# 03_-_MPU6050_Schematic.net
KiCad netlist of a schematic drawn in Altium Designer
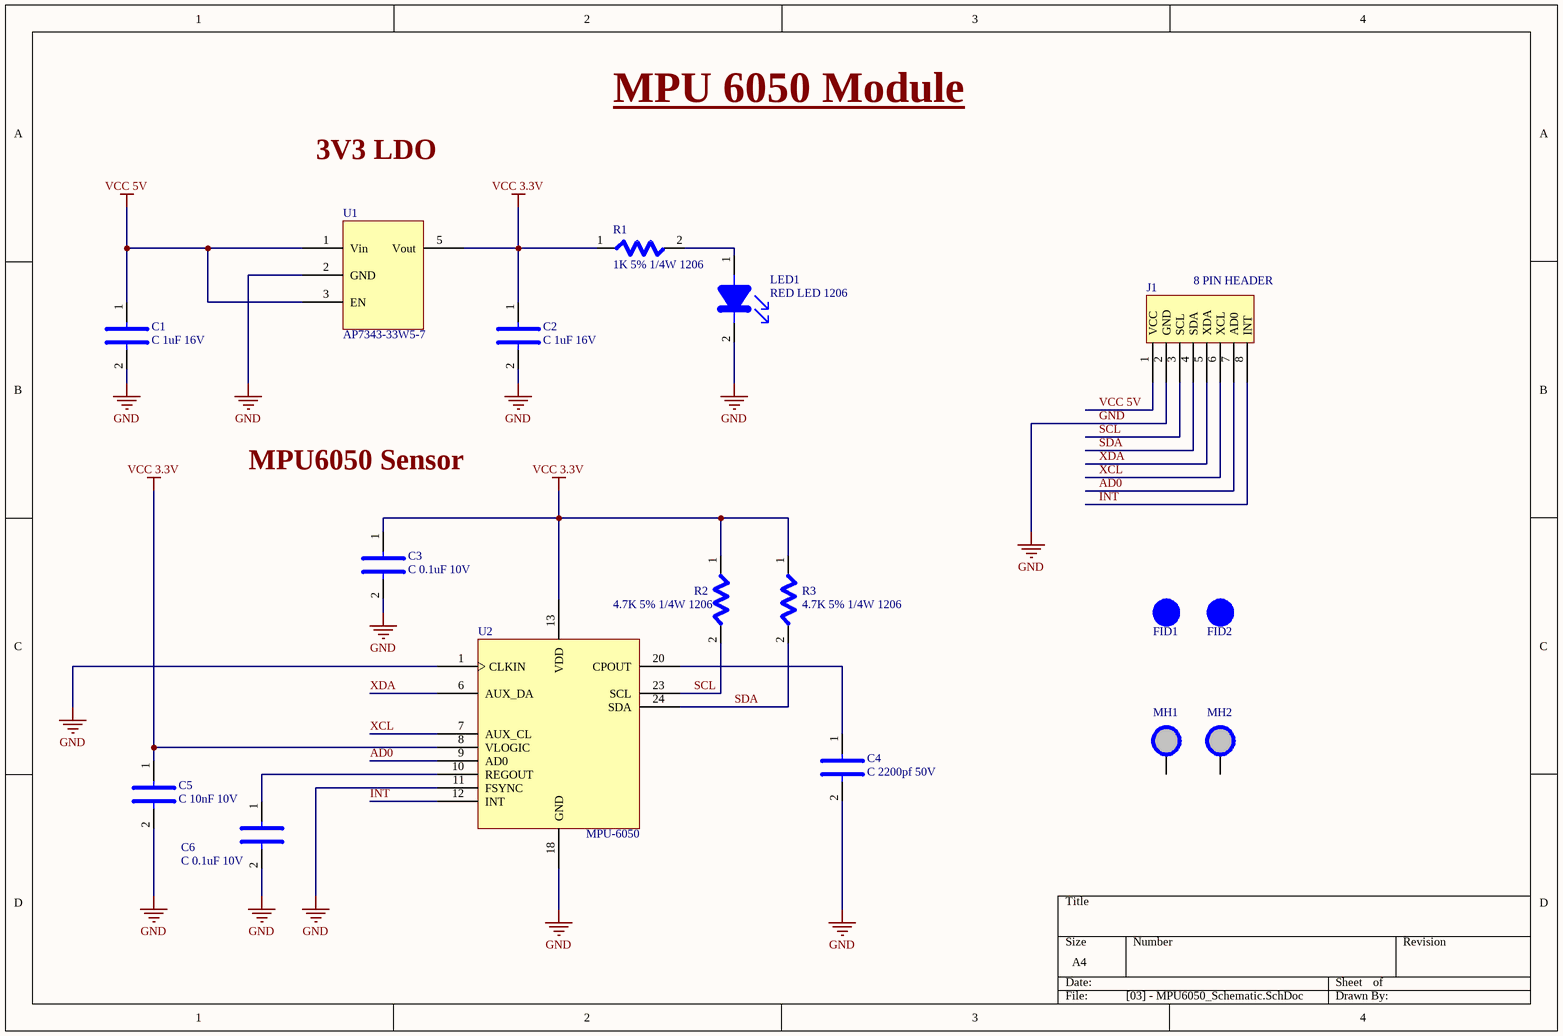
[diagram p0: [03] - MPU6050_Schematic.SchDoc]

(export (version "E")
  (design (tool "Eeschema 10.0.6"))
  (components
    (comp (ref "C1")
      (value "C 1uF 16V")
      (footprint "CAP CER 1UF 10V X7R 1206")
      (description "1 µF ±10% 10V Capacitores cerámicos X7R 1206 (3216 métrico)")
      (fields (field (name "MANUFACTURER") "KEMET"))
      (libsource (lib "MPU6050_SCHLIB") (part "CAP CER 1UF 10V X7R 1206"))
    )
    (comp (ref "C2")
      (value "C 1uF 16V")
      (footprint "CAP CER 1UF 10V X7R 1206")
      (description "1 µF ±10% 10V Capacitores cerámicos X7R 1206 (3216 métrico)")
      (fields (field (name "MANUFACTURER") "KEMET"))
      (libsource (lib "MPU6050_SCHLIB") (part "CAP CER 1UF 10V X7R 1206"))
    )
    (comp (ref "C3")
      (value "C 0.1uF 10V")
      (footprint "CAP CER 0.1UF 10V X7R 1206")
      (description "0.1 µF ±10% 10V Capacitores cerámicos X7R 1206 (3216 métrico)")
      (fields (field (name "MANUFACTURER") "KEMET"))
      (libsource (lib "MPU6050_SCHLIB") (part "CAP CER 0.1UF 10V X7R 1206"))
    )
    (comp (ref "C4")
      (value "C 2200pf 50V")
      (footprint "CAP CER 2200PF 50V NP0 1206")
      (description "CAP CER 2200PF 50V NP0 1206")
      (fields (field (name "MANUFACTURER") "KEMET"))
      (libsource (lib "MPU6050_SCHLIB") (part "CAP CER 2200PF 50V NP0 1206"))
    )
    (comp (ref "C5")
      (value "C 10nF 10V")
      (footprint "CAP CER 1206 10NF 10V ULTRA STAB")
      (description "10000 pF ±1% 10V Capacitores cerámicos X8R 1206 (3216 métrico)")
      (fields (field (name "MANUFACTURER") "KEMET"))
      (libsource (lib "MPU6050_SCHLIB") (part "CAP CER 1206 10NF 10V ULTRA STAB"))
    )
    (comp (ref "C6")
      (value "C 0.1uF 10V")
      (footprint "CAP CER 0.1UF 10V X7R 1206")
      (description "0.1 µF ±10% 10V Capacitores cerámicos X7R 1206 (3216 métrico)")
      (fields (field (name "MANUFACTURER") "KEMET"))
      (libsource (lib "MPU6050_SCHLIB") (part "CAP CER 0.1UF 10V X7R 1206"))
    )
    (comp (ref "FID1")
      (value "FID_1mm")
      (footprint "FID_40_120")
      (description "Fiducial 40mil Diameter, 120mil Mask")
      (libsource (lib "MPU6050_SCHLIB") (part "FID_1mm"))
    )
    (comp (ref "FID2")
      (value "FID_1mm")
      (footprint "FID_40_120")
      (description "Fiducial 40mil Diameter, 120mil Mask")
      (libsource (lib "MPU6050_SCHLIB") (part "FID_1mm"))
    )
    (comp (ref "J1")
      (value "8 PIN HEADER")
      (footprint "CONN HEADER VERT 8POS 3.96MM")
      (description "Cabezal de conector Orificio pasante 8 posiciones 0.156\" (3.96mm)")
      (fields (field (name "MANUFACTURER") "TE Connectivity AMP Connectors"))
      (libsource (lib "MPU6050_SCHLIB") (part "CONN HEADER VERT 8POS 3.96MM"))
    )
    (comp (ref "LED1")
      (value "RED LED 1206")
      (footprint "RES SMD 1K OHM 5% 1/4W 1206")
      (description "Rojo 630nm Indicación led: discreta 1.5V 1206 (3216 métrico)")
      (fields (field (name "MANUFACTURER") "Venkel"))
      (libsource (lib "MPU6050_SCHLIB") (part "LED 1206 FLAT LENS RED"))
    )
    (comp (ref "MH1")
      (value "MH_3.2mmD")
      (footprint "MH 7.4mmD 3.2mmDirll No plated")
      (description "MH 7..4mmD 3.2mmDrill Non plated")
      (libsource (lib "MPU6050_SCHLIB") (part "MH_3.2mmD"))
    )
    (comp (ref "MH2")
      (value "MH_3.2mmD")
      (footprint "MH 7.4mmD 3.2mmDirll No plated")
      (description "MH 7..4mmD 3.2mmDrill Non plated")
      (libsource (lib "MPU6050_SCHLIB") (part "MH_3.2mmD"))
    )
    (comp (ref "R1")
      (value "1K 5% 1/4W 1206")
      (footprint "RES SMD 1K OHM 5% 1/4W 1206")
      (description "1 kOhms ±5% 0.25W, 1/4W Resistencia en microprocesador 1206 (3216 métrico) - Película gruesa")
      (fields (field (name "MANUFACTURER") "Yageo"))
      (libsource (lib "MPU6050_SCHLIB") (part "RES SMD 1K OHM 5% 1/4W 1206"))
    )
    (comp (ref "R2")
      (value "4.7K 5% 1/4W 1206")
      (footprint "RES SMD 4.7K OHM 5% 1/4W 1206")
      (fields (field (name "MANUFACTURER") "Yageo"))
      (libsource (lib "MPU6050_SCHLIB") (part "RES 4.7K OHM 5% 1/4W 1206"))
    )
    (comp (ref "R3")
      (value "4.7K 5% 1/4W 1206")
      (footprint "RES SMD 4.7K OHM 5% 1/4W 1206")
      (fields (field (name "MANUFACTURER") "Yageo"))
      (libsource (lib "MPU6050_SCHLIB") (part "RES 4.7K OHM 5% 1/4W 1206"))
    )
    (comp (ref "U1")
      (value "AP7343-33W5-7")
      (footprint "AP7343-33W5-7")
      (description "Low dropout regulator with high output voltage. 3.3V 300mA")
      (fields (field (name "MANUFACTURER") "DIODES Incorporated"))
      (libsource (lib "MPU6050_SCHLIB") (part "AP7343-33W5-7"))
    )
    (comp (ref "U2")
      (value "MPU-6050")
      (footprint "MPU6050")
      (description "Acelerometer, gyro, 6 axis")
      (fields (field (name "MANUFACTURER") "TDK InvenSense"))
      (libsource (lib "MPU6050_SCHLIB") (part "MPU-6050"))
    )
  )
  (nets
    (net (code "1") (name "/AD0") (class "Default")
      (node (ref "J1") (pin "7") (pinfunction "AD0_7") (pintype "passive"))
      (node (ref "U2") (pin "9") (pinfunction "AD0_9") (pintype "passive"))
    )
    (net (code "2") (name "/INT") (class "Default")
      (node (ref "J1") (pin "8") (pinfunction "INT_8") (pintype "passive"))
      (node (ref "U2") (pin "12") (pinfunction "INT_12") (pintype "passive"))
    )
    (net (code "3") (name "/SCL") (class "Default")
      (node (ref "J1") (pin "3") (pinfunction "SCL_3") (pintype "passive"))
      (node (ref "R2") (pin "2") (pinfunction "2_2") (pintype "passive"))
      (node (ref "U2") (pin "23") (pinfunction "SCL_23") (pintype "passive"))
    )
    (net (code "4") (name "/SDA") (class "Default")
      (node (ref "J1") (pin "4") (pinfunction "SDA_4") (pintype "passive"))
      (node (ref "R3") (pin "2") (pinfunction "2_2") (pintype "passive"))
      (node (ref "U2") (pin "24") (pinfunction "SDA_24") (pintype "passive"))
    )
    (net (code "5") (name "/XCL") (class "Default")
      (node (ref "J1") (pin "6") (pinfunction "XCL_6") (pintype "passive"))
      (node (ref "U2") (pin "7") (pinfunction "AUX_CL_7") (pintype "passive"))
    )
    (net (code "6") (name "/XDA") (class "Default")
      (node (ref "J1") (pin "5") (pinfunction "XDA_5") (pintype "passive"))
      (node (ref "U2") (pin "6") (pinfunction "AUX_DA_6") (pintype "passive"))
    )
    (net (code "7") (name "GND") (class "Default")
      (node (ref "C1") (pin "2") (pinfunction "2_2") (pintype "passive"))
      (node (ref "C2") (pin "2") (pinfunction "2_2") (pintype "passive"))
      (node (ref "C3") (pin "2") (pinfunction "2_2") (pintype "passive"))
      (node (ref "C4") (pin "2") (pinfunction "2_2") (pintype "passive"))
      (node (ref "C5") (pin "2") (pinfunction "2_2") (pintype "passive"))
      (node (ref "C6") (pin "2") (pinfunction "2_2") (pintype "passive"))
      (node (ref "J1") (pin "2") (pinfunction "GND_2") (pintype "passive"))
      (node (ref "LED1") (pin "2") (pinfunction "2_2") (pintype "passive"))
      (node (ref "U1") (pin "2") (pinfunction "GND_2") (pintype "passive"))
      (node (ref "U2") (pin "1") (pinfunction "CLKIN_1") (pintype "passive"))
      (node (ref "U2") (pin "11") (pinfunction "FSYNC_11") (pintype "passive"))
      (node (ref "U2") (pin "18") (pinfunction "GND_18") (pintype "passive"))
    )
    (net (code "8") (name "Net-(LED1-Pad1)") (class "Default")
      (node (ref "LED1") (pin "1") (pinfunction "1_1") (pintype "passive"))
      (node (ref "R1") (pin "2") (pinfunction "2_2") (pintype "passive"))
    )
    (net (code "9") (name "Net-(U2-CPOUT)") (class "Default")
      (node (ref "C4") (pin "1") (pinfunction "1_1") (pintype "passive"))
      (node (ref "U2") (pin "20") (pinfunction "CPOUT_20") (pintype "passive"))
    )
    (net (code "10") (name "Net-(U2-REGOUT)") (class "Default")
      (node (ref "C6") (pin "1") (pinfunction "1_1") (pintype "passive"))
      (node (ref "U2") (pin "10") (pinfunction "REGOUT_10") (pintype "passive"))
    )
    (net (code "11") (name "VCC 3.3V") (class "Default")
      (node (ref "C2") (pin "1") (pinfunction "1_1") (pintype "passive"))
      (node (ref "C3") (pin "1") (pinfunction "1_1") (pintype "passive"))
      (node (ref "C5") (pin "1") (pinfunction "1_1") (pintype "passive"))
      (node (ref "R1") (pin "1") (pinfunction "1_1") (pintype "passive"))
      (node (ref "R2") (pin "1") (pinfunction "1_1") (pintype "passive"))
      (node (ref "R3") (pin "1") (pinfunction "1_1") (pintype "passive"))
      (node (ref "U1") (pin "5") (pinfunction "Vout_5") (pintype "passive"))
      (node (ref "U2") (pin "13") (pinfunction "VDD_13") (pintype "passive"))
      (node (ref "U2") (pin "8") (pinfunction "VLOGIC_8") (pintype "passive"))
    )
    (net (code "12") (name "VCC 5V") (class "Default")
      (node (ref "C1") (pin "1") (pinfunction "1_1") (pintype "passive"))
      (node (ref "J1") (pin "1") (pinfunction "VCC_1") (pintype "passive"))
      (node (ref "U1") (pin "1") (pinfunction "Vin_1") (pintype "passive"))
      (node (ref "U1") (pin "3") (pinfunction "EN_3") (pintype "passive"))
    )
    (net (code "13") (name "unconnected-(MH1-Pad1)") (class "Default")
      (node (ref "MH1") (pin "1") (pinfunction "1_1") (pintype "passive"))
    )
    (net (code "14") (name "unconnected-(MH2-Pad1)") (class "Default")
      (node (ref "MH2") (pin "1") (pinfunction "1_1") (pintype "passive"))
    )
  )
)
